# key_matrix.net
KiCad netlist of a schematic drawn in Altium Designer
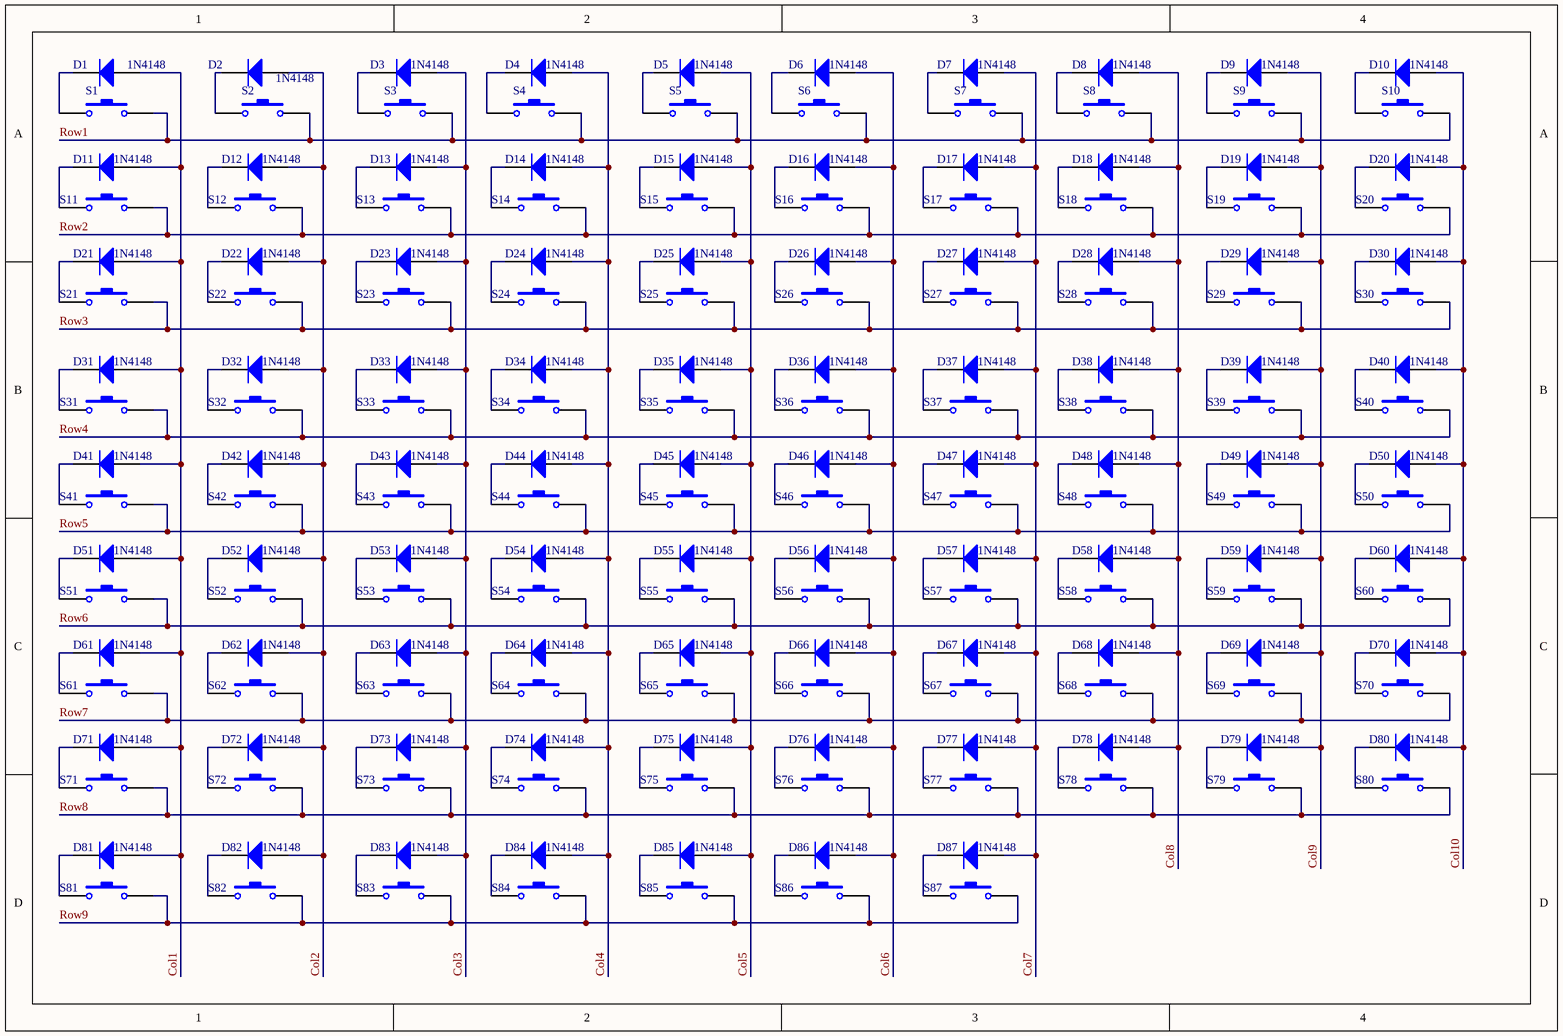
[diagram p0: key_matrix.SchDoc]

(export (version "E")
  (design (tool "Eeschema 10.0.6"))
  (components
    (comp (ref "D1")
      (value "1N4148")
      (footprint "SOD-80")
      (description "High Conductance Fast Diode")
      (fields (field (name "PUBLISHER") "Altium Limited"))
      (libsource (lib "Miscellaneous Devices") (part "Diode 1N4148"))
    )
    (comp (ref "D2")
      (value "1N4148")
      (footprint "SOD-80")
      (description "High Conductance Fast Diode")
      (fields (field (name "PUBLISHER") "Altium Limited"))
      (libsource (lib "Miscellaneous Devices") (part "Diode 1N4148"))
    )
    (comp (ref "D3")
      (value "1N4148")
      (footprint "SOD-80")
      (description "High Conductance Fast Diode")
      (fields (field (name "PUBLISHER") "Altium Limited"))
      (libsource (lib "Miscellaneous Devices") (part "Diode 1N4148"))
    )
    (comp (ref "D4")
      (value "1N4148")
      (footprint "SOD-80")
      (description "High Conductance Fast Diode")
      (fields (field (name "PUBLISHER") "Altium Limited"))
      (libsource (lib "Miscellaneous Devices") (part "Diode 1N4148"))
    )
    (comp (ref "D5")
      (value "1N4148")
      (footprint "SOD-80")
      (description "High Conductance Fast Diode")
      (fields (field (name "PUBLISHER") "Altium Limited"))
      (libsource (lib "Miscellaneous Devices") (part "Diode 1N4148"))
    )
    (comp (ref "D6")
      (value "1N4148")
      (footprint "SOD-80")
      (description "High Conductance Fast Diode")
      (fields (field (name "PUBLISHER") "Altium Limited"))
      (libsource (lib "Miscellaneous Devices") (part "Diode 1N4148"))
    )
    (comp (ref "D7")
      (value "1N4148")
      (footprint "SOD-80")
      (description "High Conductance Fast Diode")
      (fields (field (name "PUBLISHER") "Altium Limited"))
      (libsource (lib "Miscellaneous Devices") (part "Diode 1N4148"))
    )
    (comp (ref "D8")
      (value "1N4148")
      (footprint "SOD-80")
      (description "High Conductance Fast Diode")
      (fields (field (name "PUBLISHER") "Altium Limited"))
      (libsource (lib "Miscellaneous Devices") (part "Diode 1N4148"))
    )
    (comp (ref "D9")
      (value "1N4148")
      (footprint "SOD-80")
      (description "High Conductance Fast Diode")
      (fields (field (name "PUBLISHER") "Altium Limited"))
      (libsource (lib "Miscellaneous Devices") (part "Diode 1N4148"))
    )
    (comp (ref "D10")
      (value "1N4148")
      (footprint "SOD-80")
      (description "High Conductance Fast Diode")
      (fields (field (name "PUBLISHER") "Altium Limited"))
      (libsource (lib "Miscellaneous Devices") (part "Diode 1N4148"))
    )
    (comp (ref "D11")
      (value "1N4148")
      (footprint "SOD-80")
      (description "High Conductance Fast Diode")
      (fields (field (name "PUBLISHER") "Altium Limited"))
      (libsource (lib "Miscellaneous Devices") (part "Diode 1N4148"))
    )
    (comp (ref "D12")
      (value "1N4148")
      (footprint "SOD-80")
      (description "High Conductance Fast Diode")
      (fields (field (name "PUBLISHER") "Altium Limited"))
      (libsource (lib "Miscellaneous Devices") (part "Diode 1N4148"))
    )
    (comp (ref "D13")
      (value "1N4148")
      (footprint "SOD-80")
      (description "High Conductance Fast Diode")
      (fields (field (name "PUBLISHER") "Altium Limited"))
      (libsource (lib "Miscellaneous Devices") (part "Diode 1N4148"))
    )
    (comp (ref "D14")
      (value "1N4148")
      (footprint "SOD-80")
      (description "High Conductance Fast Diode")
      (fields (field (name "PUBLISHER") "Altium Limited"))
      (libsource (lib "Miscellaneous Devices") (part "Diode 1N4148"))
    )
    (comp (ref "D15")
      (value "1N4148")
      (footprint "SOD-80")
      (description "High Conductance Fast Diode")
      (fields (field (name "PUBLISHER") "Altium Limited"))
      (libsource (lib "Miscellaneous Devices") (part "Diode 1N4148"))
    )
    (comp (ref "D16")
      (value "1N4148")
      (footprint "SOD-80")
      (description "High Conductance Fast Diode")
      (fields (field (name "PUBLISHER") "Altium Limited"))
      (libsource (lib "Miscellaneous Devices") (part "Diode 1N4148"))
    )
    (comp (ref "D17")
      (value "1N4148")
      (footprint "SOD-80")
      (description "High Conductance Fast Diode")
      (fields (field (name "PUBLISHER") "Altium Limited"))
      (libsource (lib "Miscellaneous Devices") (part "Diode 1N4148"))
    )
    (comp (ref "D18")
      (value "1N4148")
      (footprint "SOD-80")
      (description "High Conductance Fast Diode")
      (fields (field (name "PUBLISHER") "Altium Limited"))
      (libsource (lib "Miscellaneous Devices") (part "Diode 1N4148"))
    )
    (comp (ref "D19")
      (value "1N4148")
      (footprint "SOD-80")
      (description "High Conductance Fast Diode")
      (fields (field (name "PUBLISHER") "Altium Limited"))
      (libsource (lib "Miscellaneous Devices") (part "Diode 1N4148"))
    )
    (comp (ref "D20")
      (value "1N4148")
      (footprint "SOD-80")
      (description "High Conductance Fast Diode")
      (fields (field (name "PUBLISHER") "Altium Limited"))
      (libsource (lib "Miscellaneous Devices") (part "Diode 1N4148"))
    )
    (comp (ref "D21")
      (value "1N4148")
      (footprint "SOD-80")
      (description "High Conductance Fast Diode")
      (fields (field (name "PUBLISHER") "Altium Limited"))
      (libsource (lib "Miscellaneous Devices") (part "Diode 1N4148"))
    )
    (comp (ref "D22")
      (value "1N4148")
      (footprint "SOD-80")
      (description "High Conductance Fast Diode")
      (fields (field (name "PUBLISHER") "Altium Limited"))
      (libsource (lib "Miscellaneous Devices") (part "Diode 1N4148"))
    )
    (comp (ref "D23")
      (value "1N4148")
      (footprint "SOD-80")
      (description "High Conductance Fast Diode")
      (fields (field (name "PUBLISHER") "Altium Limited"))
      (libsource (lib "Miscellaneous Devices") (part "Diode 1N4148"))
    )
    (comp (ref "D24")
      (value "1N4148")
      (footprint "SOD-80")
      (description "High Conductance Fast Diode")
      (fields (field (name "PUBLISHER") "Altium Limited"))
      (libsource (lib "Miscellaneous Devices") (part "Diode 1N4148"))
    )
    (comp (ref "D25")
      (value "1N4148")
      (footprint "SOD-80")
      (description "High Conductance Fast Diode")
      (fields (field (name "PUBLISHER") "Altium Limited"))
      (libsource (lib "Miscellaneous Devices") (part "Diode 1N4148"))
    )
    (comp (ref "D26")
      (value "1N4148")
      (footprint "SOD-80")
      (description "High Conductance Fast Diode")
      (fields (field (name "PUBLISHER") "Altium Limited"))
      (libsource (lib "Miscellaneous Devices") (part "Diode 1N4148"))
    )
    (comp (ref "D27")
      (value "1N4148")
      (footprint "SOD-80")
      (description "High Conductance Fast Diode")
      (fields (field (name "PUBLISHER") "Altium Limited"))
      (libsource (lib "Miscellaneous Devices") (part "Diode 1N4148"))
    )
    (comp (ref "D28")
      (value "1N4148")
      (footprint "SOD-80")
      (description "High Conductance Fast Diode")
      (fields (field (name "PUBLISHER") "Altium Limited"))
      (libsource (lib "Miscellaneous Devices") (part "Diode 1N4148"))
    )
    (comp (ref "D29")
      (value "1N4148")
      (footprint "SOD-80")
      (description "High Conductance Fast Diode")
      (fields (field (name "PUBLISHER") "Altium Limited"))
      (libsource (lib "Miscellaneous Devices") (part "Diode 1N4148"))
    )
    (comp (ref "D30")
      (value "1N4148")
      (footprint "SOD-80")
      (description "High Conductance Fast Diode")
      (fields (field (name "PUBLISHER") "Altium Limited"))
      (libsource (lib "Miscellaneous Devices") (part "Diode 1N4148"))
    )
    (comp (ref "D31")
      (value "1N4148")
      (footprint "SOD-80")
      (description "High Conductance Fast Diode")
      (fields (field (name "PUBLISHER") "Altium Limited"))
      (libsource (lib "Miscellaneous Devices") (part "Diode 1N4148"))
    )
    (comp (ref "D32")
      (value "1N4148")
      (footprint "SOD-80")
      (description "High Conductance Fast Diode")
      (fields (field (name "PUBLISHER") "Altium Limited"))
      (libsource (lib "Miscellaneous Devices") (part "Diode 1N4148"))
    )
    (comp (ref "D33")
      (value "1N4148")
      (footprint "SOD-80")
      (description "High Conductance Fast Diode")
      (fields (field (name "PUBLISHER") "Altium Limited"))
      (libsource (lib "Miscellaneous Devices") (part "Diode 1N4148"))
    )
    (comp (ref "D34")
      (value "1N4148")
      (footprint "SOD-80")
      (description "High Conductance Fast Diode")
      (fields (field (name "PUBLISHER") "Altium Limited"))
      (libsource (lib "Miscellaneous Devices") (part "Diode 1N4148"))
    )
    (comp (ref "D35")
      (value "1N4148")
      (footprint "SOD-80")
      (description "High Conductance Fast Diode")
      (fields (field (name "PUBLISHER") "Altium Limited"))
      (libsource (lib "Miscellaneous Devices") (part "Diode 1N4148"))
    )
    (comp (ref "D36")
      (value "1N4148")
      (footprint "SOD-80")
      (description "High Conductance Fast Diode")
      (fields (field (name "PUBLISHER") "Altium Limited"))
      (libsource (lib "Miscellaneous Devices") (part "Diode 1N4148"))
    )
    (comp (ref "D37")
      (value "1N4148")
      (footprint "SOD-80")
      (description "High Conductance Fast Diode")
      (fields (field (name "PUBLISHER") "Altium Limited"))
      (libsource (lib "Miscellaneous Devices") (part "Diode 1N4148"))
    )
    (comp (ref "D38")
      (value "1N4148")
      (footprint "SOD-80")
      (description "High Conductance Fast Diode")
      (fields (field (name "PUBLISHER") "Altium Limited"))
      (libsource (lib "Miscellaneous Devices") (part "Diode 1N4148"))
    )
    (comp (ref "D39")
      (value "1N4148")
      (footprint "SOD-80")
      (description "High Conductance Fast Diode")
      (fields (field (name "PUBLISHER") "Altium Limited"))
      (libsource (lib "Miscellaneous Devices") (part "Diode 1N4148"))
    )
    (comp (ref "D40")
      (value "1N4148")
      (footprint "SOD-80")
      (description "High Conductance Fast Diode")
      (fields (field (name "PUBLISHER") "Altium Limited"))
      (libsource (lib "Miscellaneous Devices") (part "Diode 1N4148"))
    )
    (comp (ref "D41")
      (value "1N4148")
      (footprint "SOD-80")
      (description "High Conductance Fast Diode")
      (fields (field (name "PUBLISHER") "Altium Limited"))
      (libsource (lib "Miscellaneous Devices") (part "Diode 1N4148"))
    )
    (comp (ref "D42")
      (value "1N4148")
      (footprint "SOD-80")
      (description "High Conductance Fast Diode")
      (fields (field (name "PUBLISHER") "Altium Limited"))
      (libsource (lib "Miscellaneous Devices") (part "Diode 1N4148"))
    )
    (comp (ref "D43")
      (value "1N4148")
      (footprint "SOD-80")
      (description "High Conductance Fast Diode")
      (fields (field (name "PUBLISHER") "Altium Limited"))
      (libsource (lib "Miscellaneous Devices") (part "Diode 1N4148"))
    )
    (comp (ref "D44")
      (value "1N4148")
      (footprint "SOD-80")
      (description "High Conductance Fast Diode")
      (fields (field (name "PUBLISHER") "Altium Limited"))
      (libsource (lib "Miscellaneous Devices") (part "Diode 1N4148"))
    )
    (comp (ref "D45")
      (value "1N4148")
      (footprint "SOD-80")
      (description "High Conductance Fast Diode")
      (fields (field (name "PUBLISHER") "Altium Limited"))
      (libsource (lib "Miscellaneous Devices") (part "Diode 1N4148"))
    )
    (comp (ref "D46")
      (value "1N4148")
      (footprint "SOD-80")
      (description "High Conductance Fast Diode")
      (fields (field (name "PUBLISHER") "Altium Limited"))
      (libsource (lib "Miscellaneous Devices") (part "Diode 1N4148"))
    )
    (comp (ref "D47")
      (value "1N4148")
      (footprint "SOD-80")
      (description "High Conductance Fast Diode")
      (fields (field (name "PUBLISHER") "Altium Limited"))
      (libsource (lib "Miscellaneous Devices") (part "Diode 1N4148"))
    )
    (comp (ref "D48")
      (value "1N4148")
      (footprint "SOD-80")
      (description "High Conductance Fast Diode")
      (fields (field (name "PUBLISHER") "Altium Limited"))
      (libsource (lib "Miscellaneous Devices") (part "Diode 1N4148"))
    )
    (comp (ref "D49")
      (value "1N4148")
      (footprint "SOD-80")
      (description "High Conductance Fast Diode")
      (fields (field (name "PUBLISHER") "Altium Limited"))
      (libsource (lib "Miscellaneous Devices") (part "Diode 1N4148"))
    )
    (comp (ref "D50")
      (value "1N4148")
      (footprint "SOD-80")
      (description "High Conductance Fast Diode")
      (fields (field (name "PUBLISHER") "Altium Limited"))
      (libsource (lib "Miscellaneous Devices") (part "Diode 1N4148"))
    )
    (comp (ref "D51")
      (value "1N4148")
      (footprint "SOD-80")
      (description "High Conductance Fast Diode")
      (fields (field (name "PUBLISHER") "Altium Limited"))
      (libsource (lib "Miscellaneous Devices") (part "Diode 1N4148"))
    )
    (comp (ref "D52")
      (value "1N4148")
      (footprint "SOD-80")
      (description "High Conductance Fast Diode")
      (fields (field (name "PUBLISHER") "Altium Limited"))
      (libsource (lib "Miscellaneous Devices") (part "Diode 1N4148"))
    )
    (comp (ref "D53")
      (value "1N4148")
      (footprint "SOD-80")
      (description "High Conductance Fast Diode")
      (fields (field (name "PUBLISHER") "Altium Limited"))
      (libsource (lib "Miscellaneous Devices") (part "Diode 1N4148"))
    )
    (comp (ref "D54")
      (value "1N4148")
      (footprint "SOD-80")
      (description "High Conductance Fast Diode")
      (fields (field (name "PUBLISHER") "Altium Limited"))
      (libsource (lib "Miscellaneous Devices") (part "Diode 1N4148"))
    )
    (comp (ref "D55")
      (value "1N4148")
      (footprint "SOD-80")
      (description "High Conductance Fast Diode")
      (fields (field (name "PUBLISHER") "Altium Limited"))
      (libsource (lib "Miscellaneous Devices") (part "Diode 1N4148"))
    )
    (comp (ref "D56")
      (value "1N4148")
      (footprint "SOD-80")
      (description "High Conductance Fast Diode")
      (fields (field (name "PUBLISHER") "Altium Limited"))
      (libsource (lib "Miscellaneous Devices") (part "Diode 1N4148"))
    )
    (comp (ref "D57")
      (value "1N4148")
      (footprint "SOD-80")
      (description "High Conductance Fast Diode")
      (fields (field (name "PUBLISHER") "Altium Limited"))
      (libsource (lib "Miscellaneous Devices") (part "Diode 1N4148"))
    )
    (comp (ref "D58")
      (value "1N4148")
      (footprint "SOD-80")
      (description "High Conductance Fast Diode")
      (fields (field (name "PUBLISHER") "Altium Limited"))
      (libsource (lib "Miscellaneous Devices") (part "Diode 1N4148"))
    )
    (comp (ref "D59")
      (value "1N4148")
      (footprint "SOD-80")
      (description "High Conductance Fast Diode")
      (fields (field (name "PUBLISHER") "Altium Limited"))
      (libsource (lib "Miscellaneous Devices") (part "Diode 1N4148"))
    )
    (comp (ref "D60")
      (value "1N4148")
      (footprint "SOD-80")
      (description "High Conductance Fast Diode")
      (fields (field (name "PUBLISHER") "Altium Limited"))
      (libsource (lib "Miscellaneous Devices") (part "Diode 1N4148"))
    )
    (comp (ref "D61")
      (value "1N4148")
      (footprint "SOD-80")
      (description "High Conductance Fast Diode")
      (fields (field (name "PUBLISHER") "Altium Limited"))
      (libsource (lib "Miscellaneous Devices") (part "Diode 1N4148"))
    )
    (comp (ref "D62")
      (value "1N4148")
      (footprint "SOD-80")
      (description "High Conductance Fast Diode")
      (fields (field (name "PUBLISHER") "Altium Limited"))
      (libsource (lib "Miscellaneous Devices") (part "Diode 1N4148"))
    )
    (comp (ref "D63")
      (value "1N4148")
      (footprint "SOD-80")
      (description "High Conductance Fast Diode")
      (fields (field (name "PUBLISHER") "Altium Limited"))
      (libsource (lib "Miscellaneous Devices") (part "Diode 1N4148"))
    )
    (comp (ref "D64")
      (value "1N4148")
      (footprint "SOD-80")
      (description "High Conductance Fast Diode")
      (fields (field (name "PUBLISHER") "Altium Limited"))
      (libsource (lib "Miscellaneous Devices") (part "Diode 1N4148"))
    )
    (comp (ref "D65")
      (value "1N4148")
      (footprint "SOD-80")
      (description "High Conductance Fast Diode")
      (fields (field (name "PUBLISHER") "Altium Limited"))
      (libsource (lib "Miscellaneous Devices") (part "Diode 1N4148"))
    )
    (comp (ref "D66")
      (value "1N4148")
      (footprint "SOD-80")
      (description "High Conductance Fast Diode")
      (fields (field (name "PUBLISHER") "Altium Limited"))
      (libsource (lib "Miscellaneous Devices") (part "Diode 1N4148"))
    )
    (comp (ref "D67")
      (value "1N4148")
      (footprint "SOD-80")
      (description "High Conductance Fast Diode")
      (fields (field (name "PUBLISHER") "Altium Limited"))
      (libsource (lib "Miscellaneous Devices") (part "Diode 1N4148"))
    )
    (comp (ref "D68")
      (value "1N4148")
      (footprint "SOD-80")
      (description "High Conductance Fast Diode")
      (fields (field (name "PUBLISHER") "Altium Limited"))
      (libsource (lib "Miscellaneous Devices") (part "Diode 1N4148"))
    )
    (comp (ref "D69")
      (value "1N4148")
      (footprint "SOD-80")
      (description "High Conductance Fast Diode")
      (fields (field (name "PUBLISHER") "Altium Limited"))
      (libsource (lib "Miscellaneous Devices") (part "Diode 1N4148"))
    )
    (comp (ref "D70")
      (value "1N4148")
      (footprint "SOD-80")
      (description "High Conductance Fast Diode")
      (fields (field (name "PUBLISHER") "Altium Limited"))
      (libsource (lib "Miscellaneous Devices") (part "Diode 1N4148"))
    )
    (comp (ref "D71")
      (value "1N4148")
      (footprint "SOD-80")
      (description "High Conductance Fast Diode")
      (fields (field (name "PUBLISHER") "Altium Limited"))
      (libsource (lib "Miscellaneous Devices") (part "Diode 1N4148"))
    )
    (comp (ref "D72")
      (value "1N4148")
      (footprint "SOD-80")
      (description "High Conductance Fast Diode")
      (fields (field (name "PUBLISHER") "Altium Limited"))
      (libsource (lib "Miscellaneous Devices") (part "Diode 1N4148"))
    )
    (comp (ref "D73")
      (value "1N4148")
      (footprint "SOD-80")
      (description "High Conductance Fast Diode")
      (fields (field (name "PUBLISHER") "Altium Limited"))
      (libsource (lib "Miscellaneous Devices") (part "Diode 1N4148"))
    )
    (comp (ref "D74")
      (value "1N4148")
      (footprint "SOD-80")
      (description "High Conductance Fast Diode")
      (fields (field (name "PUBLISHER") "Altium Limited"))
      (libsource (lib "Miscellaneous Devices") (part "Diode 1N4148"))
    )
    (comp (ref "D75")
      (value "1N4148")
      (footprint "SOD-80")
      (description "High Conductance Fast Diode")
      (fields (field (name "PUBLISHER") "Altium Limited"))
      (libsource (lib "Miscellaneous Devices") (part "Diode 1N4148"))
    )
    (comp (ref "D76")
      (value "1N4148")
      (footprint "SOD-80")
      (description "High Conductance Fast Diode")
      (fields (field (name "PUBLISHER") "Altium Limited"))
      (libsource (lib "Miscellaneous Devices") (part "Diode 1N4148"))
    )
    (comp (ref "D77")
      (value "1N4148")
      (footprint "SOD-80")
      (description "High Conductance Fast Diode")
      (fields (field (name "PUBLISHER") "Altium Limited"))
      (libsource (lib "Miscellaneous Devices") (part "Diode 1N4148"))
    )
    (comp (ref "D78")
      (value "1N4148")
      (footprint "SOD-80")
      (description "High Conductance Fast Diode")
      (fields (field (name "PUBLISHER") "Altium Limited"))
      (libsource (lib "Miscellaneous Devices") (part "Diode 1N4148"))
    )
    (comp (ref "D79")
      (value "1N4148")
      (footprint "SOD-80")
      (description "High Conductance Fast Diode")
      (fields (field (name "PUBLISHER") "Altium Limited"))
      (libsource (lib "Miscellaneous Devices") (part "Diode 1N4148"))
    )
    (comp (ref "D80")
      (value "1N4148")
      (footprint "SOD-80")
      (description "High Conductance Fast Diode")
      (fields (field (name "PUBLISHER") "Altium Limited"))
      (libsource (lib "Miscellaneous Devices") (part "Diode 1N4148"))
    )
    (comp (ref "D81")
      (value "1N4148")
      (footprint "SOD-80")
      (description "High Conductance Fast Diode")
      (fields (field (name "PUBLISHER") "Altium Limited"))
      (libsource (lib "Miscellaneous Devices") (part "Diode 1N4148"))
    )
    (comp (ref "D82")
      (value "1N4148")
      (footprint "SOD-80")
      (description "High Conductance Fast Diode")
      (fields (field (name "PUBLISHER") "Altium Limited"))
      (libsource (lib "Miscellaneous Devices") (part "Diode 1N4148"))
    )
    (comp (ref "D83")
      (value "1N4148")
      (footprint "SOD-80")
      (description "High Conductance Fast Diode")
      (fields (field (name "PUBLISHER") "Altium Limited"))
      (libsource (lib "Miscellaneous Devices") (part "Diode 1N4148"))
    )
    (comp (ref "D84")
      (value "1N4148")
      (footprint "SOD-80")
      (description "High Conductance Fast Diode")
      (fields (field (name "PUBLISHER") "Altium Limited"))
      (libsource (lib "Miscellaneous Devices") (part "Diode 1N4148"))
    )
    (comp (ref "D85")
      (value "1N4148")
      (footprint "SOD-80")
      (description "High Conductance Fast Diode")
      (fields (field (name "PUBLISHER") "Altium Limited"))
      (libsource (lib "Miscellaneous Devices") (part "Diode 1N4148"))
    )
    (comp (ref "D86")
      (value "1N4148")
      (footprint "SOD-80")
      (description "High Conductance Fast Diode")
      (fields (field (name "PUBLISHER") "Altium Limited"))
      (libsource (lib "Miscellaneous Devices") (part "Diode 1N4148"))
    )
    (comp (ref "D87")
      (value "1N4148")
      (footprint "SOD-80")
      (description "High Conductance Fast Diode")
      (fields (field (name "PUBLISHER") "Altium Limited"))
      (libsource (lib "Miscellaneous Devices") (part "Diode 1N4148"))
    )
    (comp (ref "S1")
      (value "SW-PB")
      (footprint "MX_SW-1")
      (description "Switch")
      (fields (field (name "PUBLISHER") "Altium Limited"))
      (libsource (lib "Miscellaneous Devices") (part "SW-PB"))
    )
    (comp (ref "S2")
      (value "SW-PB")
      (footprint "MX_SW-1")
      (description "Switch")
      (fields (field (name "PUBLISHER") "Altium Limited"))
      (libsource (lib "Miscellaneous Devices") (part "SW-PB"))
    )
    (comp (ref "S3")
      (value "SW-PB")
      (footprint "MX_SW-1")
      (description "Switch")
      (fields (field (name "PUBLISHER") "Altium Limited"))
      (libsource (lib "Miscellaneous Devices") (part "SW-PB"))
    )
    (comp (ref "S4")
      (value "SW-PB")
      (footprint "MX_SW-1")
      (description "Switch")
      (fields (field (name "PUBLISHER") "Altium Limited"))
      (libsource (lib "Miscellaneous Devices") (part "SW-PB"))
    )
    (comp (ref "S5")
      (value "SW-PB")
      (footprint "MX_SW-1")
      (description "Switch")
      (fields (field (name "PUBLISHER") "Altium Limited"))
      (libsource (lib "Miscellaneous Devices") (part "SW-PB"))
    )
    (comp (ref "S6")
      (value "SW-PB")
      (footprint "MX_SW-1")
      (description "Switch")
      (fields (field (name "PUBLISHER") "Altium Limited"))
      (libsource (lib "Miscellaneous Devices") (part "SW-PB"))
    )
    (comp (ref "S7")
      (value "SW-PB")
      (footprint "MX_SW-1")
      (description "Switch")
      (fields (field (name "PUBLISHER") "Altium Limited"))
      (libsource (lib "Miscellaneous Devices") (part "SW-PB"))
    )
    (comp (ref "S8")
      (value "SW-PB")
      (footprint "MX_SW-1")
      (description "Switch")
      (fields (field (name "PUBLISHER") "Altium Limited"))
      (libsource (lib "Miscellaneous Devices") (part "SW-PB"))
    )
    (comp (ref "S9")
      (value "SW-PB")
      (footprint "MX_SW-1")
      (description "Switch")
      (fields (field (name "PUBLISHER") "Altium Limited"))
      (libsource (lib "Miscellaneous Devices") (part "SW-PB"))
    )
    (comp (ref "S10")
      (value "SW-PB")
      (footprint "MX_SW-1")
      (description "Switch")
      (fields (field (name "PUBLISHER") "Altium Limited"))
      (libsource (lib "Miscellaneous Devices") (part "SW-PB"))
    )
    (comp (ref "S11")
      (value "SW-PB")
      (footprint "MX_SW-1")
      (description "Switch")
      (fields (field (name "PUBLISHER") "Altium Limited"))
      (libsource (lib "Miscellaneous Devices") (part "SW-PB"))
    )
    (comp (ref "S12")
      (value "SW-PB")
      (footprint "MX_SW-1")
      (description "Switch")
      (fields (field (name "PUBLISHER") "Altium Limited"))
      (libsource (lib "Miscellaneous Devices") (part "SW-PB"))
    )
    (comp (ref "S13")
      (value "SW-PB")
      (footprint "MX_SW-1")
      (description "Switch")
      (fields (field (name "PUBLISHER") "Altium Limited"))
      (libsource (lib "Miscellaneous Devices") (part "SW-PB"))
    )
    (comp (ref "S14")
      (value "SW-PB")
      (footprint "MX_SW-1")
      (description "Switch")
      (fields (field (name "PUBLISHER") "Altium Limited"))
      (libsource (lib "Miscellaneous Devices") (part "SW-PB"))
    )
    (comp (ref "S15")
      (value "SW-PB")
      (footprint "MX_SW-1")
      (description "Switch")
      (fields (field (name "PUBLISHER") "Altium Limited"))
      (libsource (lib "Miscellaneous Devices") (part "SW-PB"))
    )
    (comp (ref "S16")
      (value "SW-PB")
      (footprint "MX_SW-1")
      (description "Switch")
      (fields (field (name "PUBLISHER") "Altium Limited"))
      (libsource (lib "Miscellaneous Devices") (part "SW-PB"))
    )
    (comp (ref "S17")
      (value "SW-PB")
      (footprint "MX_SW-1")
      (description "Switch")
      (fields (field (name "PUBLISHER") "Altium Limited"))
      (libsource (lib "Miscellaneous Devices") (part "SW-PB"))
    )
    (comp (ref "S18")
      (value "SW-PB")
      (footprint "MX_SW-1")
      (description "Switch")
      (fields (field (name "PUBLISHER") "Altium Limited"))
      (libsource (lib "Miscellaneous Devices") (part "SW-PB"))
    )
    (comp (ref "S19")
      (value "SW-PB")
      (footprint "MX_SW-1")
      (description "Switch")
      (fields (field (name "PUBLISHER") "Altium Limited"))
      (libsource (lib "Miscellaneous Devices") (part "SW-PB"))
    )
    (comp (ref "S20")
      (value "SW-PB")
      (footprint "MX_SW-1")
      (description "Switch")
      (fields (field (name "PUBLISHER") "Altium Limited"))
      (libsource (lib "Miscellaneous Devices") (part "SW-PB"))
    )
    (comp (ref "S21")
      (value "SW-PB")
      (footprint "MX_SW-1")
      (description "Switch")
      (fields (field (name "PUBLISHER") "Altium Limited"))
      (libsource (lib "Miscellaneous Devices") (part "SW-PB"))
    )
    (comp (ref "S22")
      (value "SW-PB")
      (footprint "MX_SW-1")
      (description "Switch")
      (fields (field (name "PUBLISHER") "Altium Limited"))
      (libsource (lib "Miscellaneous Devices") (part "SW-PB"))
    )
    (comp (ref "S23")
      (value "SW-PB")
      (footprint "MX_SW-1")
      (description "Switch")
      (fields (field (name "PUBLISHER") "Altium Limited"))
      (libsource (lib "Miscellaneous Devices") (part "SW-PB"))
    )
    (comp (ref "S24")
      (value "SW-PB")
      (footprint "MX_SW-1")
      (description "Switch")
      (fields (field (name "PUBLISHER") "Altium Limited"))
      (libsource (lib "Miscellaneous Devices") (part "SW-PB"))
    )
    (comp (ref "S25")
      (value "SW-PB")
      (footprint "MX_SW-1")
      (description "Switch")
      (fields (field (name "PUBLISHER") "Altium Limited"))
      (libsource (lib "Miscellaneous Devices") (part "SW-PB"))
    )
    (comp (ref "S26")
      (value "SW-PB")
      (footprint "MX_SW-1")
      (description "Switch")
      (fields (field (name "PUBLISHER") "Altium Limited"))
      (libsource (lib "Miscellaneous Devices") (part "SW-PB"))
    )
    (comp (ref "S27")
      (value "SW-PB")
      (footprint "MX_SW-1")
      (description "Switch")
      (fields (field (name "PUBLISHER") "Altium Limited"))
      (libsource (lib "Miscellaneous Devices") (part "SW-PB"))
    )
    (comp (ref "S28")
      (value "SW-PB")
      (footprint "MX_SW-1")
      (description "Switch")
      (fields (field (name "PUBLISHER") "Altium Limited"))
      (libsource (lib "Miscellaneous Devices") (part "SW-PB"))
    )
    (comp (ref "S29")
      (value "SW-PB")
      (footprint "MX_SW-1")
      (description "Switch")
      (fields (field (name "PUBLISHER") "Altium Limited"))
      (libsource (lib "Miscellaneous Devices") (part "SW-PB"))
    )
    (comp (ref "S30")
      (value "SW-PB")
      (footprint "MX_SW-1")
      (description "Switch")
      (fields (field (name "PUBLISHER") "Altium Limited"))
      (libsource (lib "Miscellaneous Devices") (part "SW-PB"))
    )
    (comp (ref "S31")
      (value "SW-PB")
      (footprint "MX_SW-1")
      (description "Switch")
      (fields (field (name "PUBLISHER") "Altium Limited"))
      (libsource (lib "Miscellaneous Devices") (part "SW-PB"))
    )
    (comp (ref "S32")
      (value "SW-PB")
      (footprint "MX_SW-1")
      (description "Switch")
      (fields (field (name "PUBLISHER") "Altium Limited"))
      (libsource (lib "Miscellaneous Devices") (part "SW-PB"))
    )
    (comp (ref "S33")
      (value "SW-PB")
      (footprint "MX_SW-1")
      (description "Switch")
      (fields (field (name "PUBLISHER") "Altium Limited"))
      (libsource (lib "Miscellaneous Devices") (part "SW-PB"))
    )
    (comp (ref "S34")
      (value "SW-PB")
      (footprint "MX_SW-1")
      (description "Switch")
      (fields (field (name "PUBLISHER") "Altium Limited"))
      (libsource (lib "Miscellaneous Devices") (part "SW-PB"))
    )
    (comp (ref "S35")
      (value "SW-PB")
      (footprint "MX_SW-1")
      (description "Switch")
      (fields (field (name "PUBLISHER") "Altium Limited"))
      (libsource (lib "Miscellaneous Devices") (part "SW-PB"))
    )
    (comp (ref "S36")
      (value "SW-PB")
      (footprint "MX_SW-1")
      (description "Switch")
      (fields (field (name "PUBLISHER") "Altium Limited"))
      (libsource (lib "Miscellaneous Devices") (part "SW-PB"))
    )
    (comp (ref "S37")
      (value "SW-PB")
      (footprint "MX_SW-1")
      (description "Switch")
      (fields (field (name "PUBLISHER") "Altium Limited"))
      (libsource (lib "Miscellaneous Devices") (part "SW-PB"))
    )
    (comp (ref "S38")
      (value "SW-PB")
      (footprint "MX_SW-1")
      (description "Switch")
      (fields (field (name "PUBLISHER") "Altium Limited"))
      (libsource (lib "Miscellaneous Devices") (part "SW-PB"))
    )
    (comp (ref "S39")
      (value "SW-PB")
      (footprint "MX_SW-1")
      (description "Switch")
      (fields (field (name "PUBLISHER") "Altium Limited"))
      (libsource (lib "Miscellaneous Devices") (part "SW-PB"))
    )
    (comp (ref "S40")
      (value "SW-PB")
      (footprint "MX_SW-1")
      (description "Switch")
      (fields (field (name "PUBLISHER") "Altium Limited"))
      (libsource (lib "Miscellaneous Devices") (part "SW-PB"))
    )
    (comp (ref "S41")
      (value "SW-PB")
      (footprint "MX_SW-1")
      (description "Switch")
      (fields (field (name "PUBLISHER") "Altium Limited"))
      (libsource (lib "Miscellaneous Devices") (part "SW-PB"))
    )
    (comp (ref "S42")
      (value "SW-PB")
      (footprint "MX_SW-1")
      (description "Switch")
      (fields (field (name "PUBLISHER") "Altium Limited"))
      (libsource (lib "Miscellaneous Devices") (part "SW-PB"))
    )
    (comp (ref "S43")
      (value "SW-PB")
      (footprint "MX_SW-1")
      (description "Switch")
      (fields (field (name "PUBLISHER") "Altium Limited"))
      (libsource (lib "Miscellaneous Devices") (part "SW-PB"))
    )
    (comp (ref "S44")
      (value "SW-PB")
      (footprint "MX_SW-1")
      (description "Switch")
      (fields (field (name "PUBLISHER") "Altium Limited"))
      (libsource (lib "Miscellaneous Devices") (part "SW-PB"))
    )
    (comp (ref "S45")
      (value "SW-PB")
      (footprint "MX_SW-1")
      (description "Switch")
      (fields (field (name "PUBLISHER") "Altium Limited"))
      (libsource (lib "Miscellaneous Devices") (part "SW-PB"))
    )
    (comp (ref "S46")
      (value "SW-PB")
      (footprint "MX_SW-1")
      (description "Switch")
      (fields (field (name "PUBLISHER") "Altium Limited"))
      (libsource (lib "Miscellaneous Devices") (part "SW-PB"))
    )
    (comp (ref "S47")
      (value "SW-PB")
      (footprint "MX_SW-1")
      (description "Switch")
      (fields (field (name "PUBLISHER") "Altium Limited"))
      (libsource (lib "Miscellaneous Devices") (part "SW-PB"))
    )
    (comp (ref "S48")
      (value "SW-PB")
      (footprint "MX_SW-1")
      (description "Switch")
      (fields (field (name "PUBLISHER") "Altium Limited"))
      (libsource (lib "Miscellaneous Devices") (part "SW-PB"))
    )
    (comp (ref "S49")
      (value "SW-PB")
      (footprint "MX_SW-1")
      (description "Switch")
      (fields (field (name "PUBLISHER") "Altium Limited"))
      (libsource (lib "Miscellaneous Devices") (part "SW-PB"))
    )
    (comp (ref "S50")
      (value "SW-PB")
      (footprint "MX_SW-1")
      (description "Switch")
      (fields (field (name "PUBLISHER") "Altium Limited"))
      (libsource (lib "Miscellaneous Devices") (part "SW-PB"))
    )
    (comp (ref "S51")
      (value "SW-PB")
      (footprint "MX_SW-1")
      (description "Switch")
      (fields (field (name "PUBLISHER") "Altium Limited"))
      (libsource (lib "Miscellaneous Devices") (part "SW-PB"))
    )
    (comp (ref "S52")
      (value "SW-PB")
      (footprint "MX_SW-1")
      (description "Switch")
      (fields (field (name "PUBLISHER") "Altium Limited"))
      (libsource (lib "Miscellaneous Devices") (part "SW-PB"))
    )
    (comp (ref "S53")
      (value "SW-PB")
      (footprint "MX_SW-1")
      (description "Switch")
      (fields (field (name "PUBLISHER") "Altium Limited"))
      (libsource (lib "Miscellaneous Devices") (part "SW-PB"))
    )
    (comp (ref "S54")
      (value "SW-PB")
      (footprint "MX_SW-1")
      (description "Switch")
      (fields (field (name "PUBLISHER") "Altium Limited"))
      (libsource (lib "Miscellaneous Devices") (part "SW-PB"))
    )
    (comp (ref "S55")
      (value "SW-PB")
      (footprint "MX_SW-1")
      (description "Switch")
      (fields (field (name "PUBLISHER") "Altium Limited"))
      (libsource (lib "Miscellaneous Devices") (part "SW-PB"))
    )
    (comp (ref "S56")
      (value "SW-PB")
      (footprint "MX_SW-1")
      (description "Switch")
      (fields (field (name "PUBLISHER") "Altium Limited"))
      (libsource (lib "Miscellaneous Devices") (part "SW-PB"))
    )
    (comp (ref "S57")
      (value "SW-PB")
      (footprint "MX_SW-1")
      (description "Switch")
      (fields (field (name "PUBLISHER") "Altium Limited"))
      (libsource (lib "Miscellaneous Devices") (part "SW-PB"))
    )
    (comp (ref "S58")
      (value "SW-PB")
      (footprint "MX_SW-1")
      (description "Switch")
      (fields (field (name "PUBLISHER") "Altium Limited"))
      (libsource (lib "Miscellaneous Devices") (part "SW-PB"))
    )
    (comp (ref "S59")
      (value "SW-PB")
      (footprint "MX_SW-1")
      (description "Switch")
      (fields (field (name "PUBLISHER") "Altium Limited"))
      (libsource (lib "Miscellaneous Devices") (part "SW-PB"))
    )
    (comp (ref "S60")
      (value "SW-PB")
      (footprint "MX_SW-1")
      (description "Switch")
      (fields (field (name "PUBLISHER") "Altium Limited"))
      (libsource (lib "Miscellaneous Devices") (part "SW-PB"))
    )
    (comp (ref "S61")
      (value "SW-PB")
      (footprint "MX_SW-1")
      (description "Switch")
      (fields (field (name "PUBLISHER") "Altium Limited"))
      (libsource (lib "Miscellaneous Devices") (part "SW-PB"))
    )
    (comp (ref "S62")
      (value "SW-PB")
      (footprint "MX_SW-1")
      (description "Switch")
      (fields (field (name "PUBLISHER") "Altium Limited"))
      (libsource (lib "Miscellaneous Devices") (part "SW-PB"))
    )
    (comp (ref "S63")
      (value "SW-PB")
      (footprint "MX_SW-1")
      (description "Switch")
      (fields (field (name "PUBLISHER") "Altium Limited"))
      (libsource (lib "Miscellaneous Devices") (part "SW-PB"))
    )
    (comp (ref "S64")
      (value "SW-PB")
      (footprint "MX_SW-1")
      (description "Switch")
      (fields (field (name "PUBLISHER") "Altium Limited"))
      (libsource (lib "Miscellaneous Devices") (part "SW-PB"))
    )
    (comp (ref "S65")
      (value "SW-PB")
      (footprint "MX_SW-1")
      (description "Switch")
      (fields (field (name "PUBLISHER") "Altium Limited"))
      (libsource (lib "Miscellaneous Devices") (part "SW-PB"))
    )
    (comp (ref "S66")
      (value "SW-PB")
      (footprint "MX_SW-1")
      (description "Switch")
      (fields (field (name "PUBLISHER") "Altium Limited"))
      (libsource (lib "Miscellaneous Devices") (part "SW-PB"))
    )
    (comp (ref "S67")
      (value "SW-PB")
      (footprint "MX_SW-1")
      (description "Switch")
      (fields (field (name "PUBLISHER") "Altium Limited"))
      (libsource (lib "Miscellaneous Devices") (part "SW-PB"))
    )
    (comp (ref "S68")
      (value "SW-PB")
      (footprint "MX_SW-1")
      (description "Switch")
      (fields (field (name "PUBLISHER") "Altium Limited"))
      (libsource (lib "Miscellaneous Devices") (part "SW-PB"))
    )
    (comp (ref "S69")
      (value "SW-PB")
      (footprint "MX_SW-1")
      (description "Switch")
      (fields (field (name "PUBLISHER") "Altium Limited"))
      (libsource (lib "Miscellaneous Devices") (part "SW-PB"))
    )
    (comp (ref "S70")
      (value "SW-PB")
      (footprint "MX_SW-1")
      (description "Switch")
      (fields (field (name "PUBLISHER") "Altium Limited"))
      (libsource (lib "Miscellaneous Devices") (part "SW-PB"))
    )
    (comp (ref "S71")
      (value "SW-PB")
      (footprint "MX_SW-1")
      (description "Switch")
      (fields (field (name "PUBLISHER") "Altium Limited"))
      (libsource (lib "Miscellaneous Devices") (part "SW-PB"))
    )
    (comp (ref "S72")
      (value "SW-PB")
      (footprint "MX_SW-1")
      (description "Switch")
      (fields (field (name "PUBLISHER") "Altium Limited"))
      (libsource (lib "Miscellaneous Devices") (part "SW-PB"))
    )
    (comp (ref "S73")
      (value "SW-PB")
      (footprint "MX_SW-1")
      (description "Switch")
      (fields (field (name "PUBLISHER") "Altium Limited"))
      (libsource (lib "Miscellaneous Devices") (part "SW-PB"))
    )
    (comp (ref "S74")
      (value "SW-PB")
      (footprint "MX_SW-1")
      (description "Switch")
      (fields (field (name "PUBLISHER") "Altium Limited"))
      (libsource (lib "Miscellaneous Devices") (part "SW-PB"))
    )
    (comp (ref "S75")
      (value "SW-PB")
      (footprint "MX_SW-1")
      (description "Switch")
      (fields (field (name "PUBLISHER") "Altium Limited"))
      (libsource (lib "Miscellaneous Devices") (part "SW-PB"))
    )
    (comp (ref "S76")
      (value "SW-PB")
      (footprint "MX_SW-1")
      (description "Switch")
      (fields (field (name "PUBLISHER") "Altium Limited"))
      (libsource (lib "Miscellaneous Devices") (part "SW-PB"))
    )
    (comp (ref "S77")
      (value "SW-PB")
      (footprint "MX_SW-1")
      (description "Switch")
      (fields (field (name "PUBLISHER") "Altium Limited"))
      (libsource (lib "Miscellaneous Devices") (part "SW-PB"))
    )
    (comp (ref "S78")
      (value "SW-PB")
      (footprint "MX_SW-1")
      (description "Switch")
      (fields (field (name "PUBLISHER") "Altium Limited"))
      (libsource (lib "Miscellaneous Devices") (part "SW-PB"))
    )
    (comp (ref "S79")
      (value "SW-PB")
      (footprint "MX_SW-1")
      (description "Switch")
      (fields (field (name "PUBLISHER") "Altium Limited"))
      (libsource (lib "Miscellaneous Devices") (part "SW-PB"))
    )
    (comp (ref "S80")
      (value "SW-PB")
      (footprint "MX_SW-1")
      (description "Switch")
      (fields (field (name "PUBLISHER") "Altium Limited"))
      (libsource (lib "Miscellaneous Devices") (part "SW-PB"))
    )
    (comp (ref "S81")
      (value "SW-PB")
      (footprint "MX_SW-1")
      (description "Switch")
      (fields (field (name "PUBLISHER") "Altium Limited"))
      (libsource (lib "Miscellaneous Devices") (part "SW-PB"))
    )
    (comp (ref "S82")
      (value "SW-PB")
      (footprint "MX_SW-1")
      (description "Switch")
      (fields (field (name "PUBLISHER") "Altium Limited"))
      (libsource (lib "Miscellaneous Devices") (part "SW-PB"))
    )
    (comp (ref "S83")
      (value "SW-PB")
      (footprint "MX_SW-1")
      (description "Switch")
      (fields (field (name "PUBLISHER") "Altium Limited"))
      (libsource (lib "Miscellaneous Devices") (part "SW-PB"))
    )
    (comp (ref "S84")
      (value "SW-PB")
      (footprint "MX_SW-1")
      (description "Switch")
      (fields (field (name "PUBLISHER") "Altium Limited"))
      (libsource (lib "Miscellaneous Devices") (part "SW-PB"))
    )
    (comp (ref "S85")
      (value "SW-PB")
      (footprint "MX_SW-1")
      (description "Switch")
      (fields (field (name "PUBLISHER") "Altium Limited"))
      (libsource (lib "Miscellaneous Devices") (part "SW-PB"))
    )
    (comp (ref "S86")
      (value "SW-PB")
      (footprint "MX_SW-1")
      (description "Switch")
      (fields (field (name "PUBLISHER") "Altium Limited"))
      (libsource (lib "Miscellaneous Devices") (part "SW-PB"))
    )
    (comp (ref "S87")
      (value "SW-PB")
      (footprint "MX_SW-1")
      (description "Switch")
      (fields (field (name "PUBLISHER") "Altium Limited"))
      (libsource (lib "Miscellaneous Devices") (part "SW-PB"))
    )
  )
  (nets
    (net (code "1") (name "/Col1") (class "Default")
      (node (ref "D1") (pin "1") (pinfunction "A_1") (pintype "passive"))
      (node (ref "D11") (pin "1") (pinfunction "A_1") (pintype "passive"))
      (node (ref "D21") (pin "1") (pinfunction "A_1") (pintype "passive"))
      (node (ref "D31") (pin "1") (pinfunction "A_1") (pintype "passive"))
      (node (ref "D41") (pin "1") (pinfunction "A_1") (pintype "passive"))
      (node (ref "D51") (pin "1") (pinfunction "A_1") (pintype "passive"))
      (node (ref "D61") (pin "1") (pinfunction "A_1") (pintype "passive"))
      (node (ref "D71") (pin "1") (pinfunction "A_1") (pintype "passive"))
      (node (ref "D81") (pin "1") (pinfunction "A_1") (pintype "passive"))
    )
    (net (code "2") (name "/Col2") (class "Default")
      (node (ref "D12") (pin "1") (pinfunction "A_1") (pintype "passive"))
      (node (ref "D2") (pin "1") (pinfunction "A_1") (pintype "passive"))
      (node (ref "D22") (pin "1") (pinfunction "A_1") (pintype "passive"))
      (node (ref "D32") (pin "1") (pinfunction "A_1") (pintype "passive"))
      (node (ref "D42") (pin "1") (pinfunction "A_1") (pintype "passive"))
      (node (ref "D52") (pin "1") (pinfunction "A_1") (pintype "passive"))
      (node (ref "D62") (pin "1") (pinfunction "A_1") (pintype "passive"))
      (node (ref "D72") (pin "1") (pinfunction "A_1") (pintype "passive"))
      (node (ref "D82") (pin "1") (pinfunction "A_1") (pintype "passive"))
    )
    (net (code "3") (name "/Col3") (class "Default")
      (node (ref "D13") (pin "1") (pinfunction "A_1") (pintype "passive"))
      (node (ref "D23") (pin "1") (pinfunction "A_1") (pintype "passive"))
      (node (ref "D3") (pin "1") (pinfunction "A_1") (pintype "passive"))
      (node (ref "D33") (pin "1") (pinfunction "A_1") (pintype "passive"))
      (node (ref "D43") (pin "1") (pinfunction "A_1") (pintype "passive"))
      (node (ref "D53") (pin "1") (pinfunction "A_1") (pintype "passive"))
      (node (ref "D63") (pin "1") (pinfunction "A_1") (pintype "passive"))
      (node (ref "D73") (pin "1") (pinfunction "A_1") (pintype "passive"))
      (node (ref "D83") (pin "1") (pinfunction "A_1") (pintype "passive"))
    )
    (net (code "4") (name "/Col4") (class "Default")
      (node (ref "D14") (pin "1") (pinfunction "A_1") (pintype "passive"))
      (node (ref "D24") (pin "1") (pinfunction "A_1") (pintype "passive"))
      (node (ref "D34") (pin "1") (pinfunction "A_1") (pintype "passive"))
      (node (ref "D4") (pin "1") (pinfunction "A_1") (pintype "passive"))
      (node (ref "D44") (pin "1") (pinfunction "A_1") (pintype "passive"))
      (node (ref "D54") (pin "1") (pinfunction "A_1") (pintype "passive"))
      (node (ref "D64") (pin "1") (pinfunction "A_1") (pintype "passive"))
      (node (ref "D74") (pin "1") (pinfunction "A_1") (pintype "passive"))
      (node (ref "D84") (pin "1") (pinfunction "A_1") (pintype "passive"))
    )
    (net (code "5") (name "/Col5") (class "Default")
      (node (ref "D15") (pin "1") (pinfunction "A_1") (pintype "passive"))
      (node (ref "D25") (pin "1") (pinfunction "A_1") (pintype "passive"))
      (node (ref "D35") (pin "1") (pinfunction "A_1") (pintype "passive"))
      (node (ref "D45") (pin "1") (pinfunction "A_1") (pintype "passive"))
      (node (ref "D5") (pin "1") (pinfunction "A_1") (pintype "passive"))
      (node (ref "D55") (pin "1") (pinfunction "A_1") (pintype "passive"))
      (node (ref "D65") (pin "1") (pinfunction "A_1") (pintype "passive"))
      (node (ref "D75") (pin "1") (pinfunction "A_1") (pintype "passive"))
      (node (ref "D85") (pin "1") (pinfunction "A_1") (pintype "passive"))
    )
    (net (code "6") (name "/Col6") (class "Default")
      (node (ref "D16") (pin "1") (pinfunction "A_1") (pintype "passive"))
      (node (ref "D26") (pin "1") (pinfunction "A_1") (pintype "passive"))
      (node (ref "D36") (pin "1") (pinfunction "A_1") (pintype "passive"))
      (node (ref "D46") (pin "1") (pinfunction "A_1") (pintype "passive"))
      (node (ref "D56") (pin "1") (pinfunction "A_1") (pintype "passive"))
      (node (ref "D6") (pin "1") (pinfunction "A_1") (pintype "passive"))
      (node (ref "D66") (pin "1") (pinfunction "A_1") (pintype "passive"))
      (node (ref "D76") (pin "1") (pinfunction "A_1") (pintype "passive"))
      (node (ref "D86") (pin "1") (pinfunction "A_1") (pintype "passive"))
    )
    (net (code "7") (name "/Col7") (class "Default")
      (node (ref "D17") (pin "1") (pinfunction "A_1") (pintype "passive"))
      (node (ref "D27") (pin "1") (pinfunction "A_1") (pintype "passive"))
      (node (ref "D37") (pin "1") (pinfunction "A_1") (pintype "passive"))
      (node (ref "D47") (pin "1") (pinfunction "A_1") (pintype "passive"))
      (node (ref "D57") (pin "1") (pinfunction "A_1") (pintype "passive"))
      (node (ref "D67") (pin "1") (pinfunction "A_1") (pintype "passive"))
      (node (ref "D7") (pin "1") (pinfunction "A_1") (pintype "passive"))
      (node (ref "D77") (pin "1") (pinfunction "A_1") (pintype "passive"))
      (node (ref "D87") (pin "1") (pinfunction "A_1") (pintype "passive"))
    )
    (net (code "8") (name "/Col8") (class "Default")
      (node (ref "D18") (pin "1") (pinfunction "A_1") (pintype "passive"))
      (node (ref "D28") (pin "1") (pinfunction "A_1") (pintype "passive"))
      (node (ref "D38") (pin "1") (pinfunction "A_1") (pintype "passive"))
      (node (ref "D48") (pin "1") (pinfunction "A_1") (pintype "passive"))
      (node (ref "D58") (pin "1") (pinfunction "A_1") (pintype "passive"))
      (node (ref "D68") (pin "1") (pinfunction "A_1") (pintype "passive"))
      (node (ref "D78") (pin "1") (pinfunction "A_1") (pintype "passive"))
      (node (ref "D8") (pin "1") (pinfunction "A_1") (pintype "passive"))
    )
    (net (code "9") (name "/Col9") (class "Default")
      (node (ref "D19") (pin "1") (pinfunction "A_1") (pintype "passive"))
      (node (ref "D29") (pin "1") (pinfunction "A_1") (pintype "passive"))
      (node (ref "D39") (pin "1") (pinfunction "A_1") (pintype "passive"))
      (node (ref "D49") (pin "1") (pinfunction "A_1") (pintype "passive"))
      (node (ref "D59") (pin "1") (pinfunction "A_1") (pintype "passive"))
      (node (ref "D69") (pin "1") (pinfunction "A_1") (pintype "passive"))
      (node (ref "D79") (pin "1") (pinfunction "A_1") (pintype "passive"))
      (node (ref "D9") (pin "1") (pinfunction "A_1") (pintype "passive"))
    )
    (net (code "10") (name "/Col10") (class "Default")
      (node (ref "D10") (pin "1") (pinfunction "A_1") (pintype "passive"))
      (node (ref "D20") (pin "1") (pinfunction "A_1") (pintype "passive"))
      (node (ref "D30") (pin "1") (pinfunction "A_1") (pintype "passive"))
      (node (ref "D40") (pin "1") (pinfunction "A_1") (pintype "passive"))
      (node (ref "D50") (pin "1") (pinfunction "A_1") (pintype "passive"))
      (node (ref "D60") (pin "1") (pinfunction "A_1") (pintype "passive"))
      (node (ref "D70") (pin "1") (pinfunction "A_1") (pintype "passive"))
      (node (ref "D80") (pin "1") (pinfunction "A_1") (pintype "passive"))
    )
    (net (code "11") (name "/Row1") (class "Default")
      (node (ref "S1") (pin "2") (pinfunction "2_2") (pintype "passive"))
      (node (ref "S10") (pin "2") (pinfunction "2_2") (pintype "passive"))
      (node (ref "S2") (pin "2") (pinfunction "2_2") (pintype "passive"))
      (node (ref "S3") (pin "2") (pinfunction "2_2") (pintype "passive"))
      (node (ref "S4") (pin "2") (pinfunction "2_2") (pintype "passive"))
      (node (ref "S5") (pin "2") (pinfunction "2_2") (pintype "passive"))
      (node (ref "S6") (pin "2") (pinfunction "2_2") (pintype "passive"))
      (node (ref "S7") (pin "2") (pinfunction "2_2") (pintype "passive"))
      (node (ref "S8") (pin "2") (pinfunction "2_2") (pintype "passive"))
      (node (ref "S9") (pin "2") (pinfunction "2_2") (pintype "passive"))
    )
    (net (code "12") (name "/Row2") (class "Default")
      (node (ref "S11") (pin "2") (pinfunction "2_2") (pintype "passive"))
      (node (ref "S12") (pin "2") (pinfunction "2_2") (pintype "passive"))
      (node (ref "S13") (pin "2") (pinfunction "2_2") (pintype "passive"))
      (node (ref "S14") (pin "2") (pinfunction "2_2") (pintype "passive"))
      (node (ref "S15") (pin "2") (pinfunction "2_2") (pintype "passive"))
      (node (ref "S16") (pin "2") (pinfunction "2_2") (pintype "passive"))
      (node (ref "S17") (pin "2") (pinfunction "2_2") (pintype "passive"))
      (node (ref "S18") (pin "2") (pinfunction "2_2") (pintype "passive"))
      (node (ref "S19") (pin "2") (pinfunction "2_2") (pintype "passive"))
      (node (ref "S20") (pin "2") (pinfunction "2_2") (pintype "passive"))
    )
    (net (code "13") (name "/Row3") (class "Default")
      (node (ref "S21") (pin "2") (pinfunction "2_2") (pintype "passive"))
      (node (ref "S22") (pin "2") (pinfunction "2_2") (pintype "passive"))
      (node (ref "S23") (pin "2") (pinfunction "2_2") (pintype "passive"))
      (node (ref "S24") (pin "2") (pinfunction "2_2") (pintype "passive"))
      (node (ref "S25") (pin "2") (pinfunction "2_2") (pintype "passive"))
      (node (ref "S26") (pin "2") (pinfunction "2_2") (pintype "passive"))
      (node (ref "S27") (pin "2") (pinfunction "2_2") (pintype "passive"))
      (node (ref "S28") (pin "2") (pinfunction "2_2") (pintype "passive"))
      (node (ref "S29") (pin "2") (pinfunction "2_2") (pintype "passive"))
      (node (ref "S30") (pin "2") (pinfunction "2_2") (pintype "passive"))
    )
    (net (code "14") (name "/Row4") (class "Default")
      (node (ref "S31") (pin "2") (pinfunction "2_2") (pintype "passive"))
      (node (ref "S32") (pin "2") (pinfunction "2_2") (pintype "passive"))
      (node (ref "S33") (pin "2") (pinfunction "2_2") (pintype "passive"))
      (node (ref "S34") (pin "2") (pinfunction "2_2") (pintype "passive"))
      (node (ref "S35") (pin "2") (pinfunction "2_2") (pintype "passive"))
      (node (ref "S36") (pin "2") (pinfunction "2_2") (pintype "passive"))
      (node (ref "S37") (pin "2") (pinfunction "2_2") (pintype "passive"))
      (node (ref "S38") (pin "2") (pinfunction "2_2") (pintype "passive"))
      (node (ref "S39") (pin "2") (pinfunction "2_2") (pintype "passive"))
      (node (ref "S40") (pin "2") (pinfunction "2_2") (pintype "passive"))
    )
    (net (code "15") (name "/Row5") (class "Default")
      (node (ref "S41") (pin "2") (pinfunction "2_2") (pintype "passive"))
      (node (ref "S42") (pin "2") (pinfunction "2_2") (pintype "passive"))
      (node (ref "S43") (pin "2") (pinfunction "2_2") (pintype "passive"))
      (node (ref "S44") (pin "2") (pinfunction "2_2") (pintype "passive"))
      (node (ref "S45") (pin "2") (pinfunction "2_2") (pintype "passive"))
      (node (ref "S46") (pin "2") (pinfunction "2_2") (pintype "passive"))
      (node (ref "S47") (pin "2") (pinfunction "2_2") (pintype "passive"))
      (node (ref "S48") (pin "2") (pinfunction "2_2") (pintype "passive"))
      (node (ref "S49") (pin "2") (pinfunction "2_2") (pintype "passive"))
      (node (ref "S50") (pin "2") (pinfunction "2_2") (pintype "passive"))
    )
    (net (code "16") (name "/Row6") (class "Default")
      (node (ref "S51") (pin "2") (pinfunction "2_2") (pintype "passive"))
      (node (ref "S52") (pin "2") (pinfunction "2_2") (pintype "passive"))
      (node (ref "S53") (pin "2") (pinfunction "2_2") (pintype "passive"))
      (node (ref "S54") (pin "2") (pinfunction "2_2") (pintype "passive"))
      (node (ref "S55") (pin "2") (pinfunction "2_2") (pintype "passive"))
      (node (ref "S56") (pin "2") (pinfunction "2_2") (pintype "passive"))
      (node (ref "S57") (pin "2") (pinfunction "2_2") (pintype "passive"))
      (node (ref "S58") (pin "2") (pinfunction "2_2") (pintype "passive"))
      (node (ref "S59") (pin "2") (pinfunction "2_2") (pintype "passive"))
      (node (ref "S60") (pin "2") (pinfunction "2_2") (pintype "passive"))
    )
    (net (code "17") (name "/Row7") (class "Default")
      (node (ref "S61") (pin "2") (pinfunction "2_2") (pintype "passive"))
      (node (ref "S62") (pin "2") (pinfunction "2_2") (pintype "passive"))
      (node (ref "S63") (pin "2") (pinfunction "2_2") (pintype "passive"))
      (node (ref "S64") (pin "2") (pinfunction "2_2") (pintype "passive"))
      (node (ref "S65") (pin "2") (pinfunction "2_2") (pintype "passive"))
      (node (ref "S66") (pin "2") (pinfunction "2_2") (pintype "passive"))
      (node (ref "S67") (pin "2") (pinfunction "2_2") (pintype "passive"))
      (node (ref "S68") (pin "2") (pinfunction "2_2") (pintype "passive"))
      (node (ref "S69") (pin "2") (pinfunction "2_2") (pintype "passive"))
      (node (ref "S70") (pin "2") (pinfunction "2_2") (pintype "passive"))
    )
    (net (code "18") (name "/Row8") (class "Default")
      (node (ref "S71") (pin "2") (pinfunction "2_2") (pintype "passive"))
      (node (ref "S72") (pin "2") (pinfunction "2_2") (pintype "passive"))
      (node (ref "S73") (pin "2") (pinfunction "2_2") (pintype "passive"))
      (node (ref "S74") (pin "2") (pinfunction "2_2") (pintype "passive"))
      (node (ref "S75") (pin "2") (pinfunction "2_2") (pintype "passive"))
      (node (ref "S76") (pin "2") (pinfunction "2_2") (pintype "passive"))
      (node (ref "S77") (pin "2") (pinfunction "2_2") (pintype "passive"))
      (node (ref "S78") (pin "2") (pinfunction "2_2") (pintype "passive"))
      (node (ref "S79") (pin "2") (pinfunction "2_2") (pintype "passive"))
      (node (ref "S80") (pin "2") (pinfunction "2_2") (pintype "passive"))
    )
    (net (code "19") (name "/Row9") (class "Default")
      (node (ref "S81") (pin "2") (pinfunction "2_2") (pintype "passive"))
      (node (ref "S82") (pin "2") (pinfunction "2_2") (pintype "passive"))
      (node (ref "S83") (pin "2") (pinfunction "2_2") (pintype "passive"))
      (node (ref "S84") (pin "2") (pinfunction "2_2") (pintype "passive"))
      (node (ref "S85") (pin "2") (pinfunction "2_2") (pintype "passive"))
      (node (ref "S86") (pin "2") (pinfunction "2_2") (pintype "passive"))
      (node (ref "S87") (pin "2") (pinfunction "2_2") (pintype "passive"))
    )
    (net (code "20") (name "Net-(D1-K)") (class "Default")
      (node (ref "D1") (pin "2") (pinfunction "K_2") (pintype "passive"))
      (node (ref "S1") (pin "1") (pinfunction "1_1") (pintype "passive"))
    )
    (net (code "21") (name "Net-(D2-K)") (class "Default")
      (node (ref "D2") (pin "2") (pinfunction "K_2") (pintype "passive"))
      (node (ref "S2") (pin "1") (pinfunction "1_1") (pintype "passive"))
    )
    (net (code "22") (name "Net-(D3-K)") (class "Default")
      (node (ref "D3") (pin "2") (pinfunction "K_2") (pintype "passive"))
      (node (ref "S3") (pin "1") (pinfunction "1_1") (pintype "passive"))
    )
    (net (code "23") (name "Net-(D4-K)") (class "Default")
      (node (ref "D4") (pin "2") (pinfunction "K_2") (pintype "passive"))
      (node (ref "S4") (pin "1") (pinfunction "1_1") (pintype "passive"))
    )
    (net (code "24") (name "Net-(D5-K)") (class "Default")
      (node (ref "D5") (pin "2") (pinfunction "K_2") (pintype "passive"))
      (node (ref "S5") (pin "1") (pinfunction "1_1") (pintype "passive"))
    )
    (net (code "25") (name "Net-(D6-K)") (class "Default")
      (node (ref "D6") (pin "2") (pinfunction "K_2") (pintype "passive"))
      (node (ref "S6") (pin "1") (pinfunction "1_1") (pintype "passive"))
    )
    (net (code "26") (name "Net-(D7-K)") (class "Default")
      (node (ref "D7") (pin "2") (pinfunction "K_2") (pintype "passive"))
      (node (ref "S7") (pin "1") (pinfunction "1_1") (pintype "passive"))
    )
    (net (code "27") (name "Net-(D8-K)") (class "Default")
      (node (ref "D8") (pin "2") (pinfunction "K_2") (pintype "passive"))
      (node (ref "S8") (pin "1") (pinfunction "1_1") (pintype "passive"))
    )
    (net (code "28") (name "Net-(D9-K)") (class "Default")
      (node (ref "D9") (pin "2") (pinfunction "K_2") (pintype "passive"))
      (node (ref "S9") (pin "1") (pinfunction "1_1") (pintype "passive"))
    )
    (net (code "29") (name "Net-(D10-K)") (class "Default")
      (node (ref "D10") (pin "2") (pinfunction "K_2") (pintype "passive"))
      (node (ref "S10") (pin "1") (pinfunction "1_1") (pintype "passive"))
    )
    (net (code "30") (name "Net-(D11-K)") (class "Default")
      (node (ref "D11") (pin "2") (pinfunction "K_2") (pintype "passive"))
      (node (ref "S11") (pin "1") (pinfunction "1_1") (pintype "passive"))
    )
    (net (code "31") (name "Net-(D12-K)") (class "Default")
      (node (ref "D12") (pin "2") (pinfunction "K_2") (pintype "passive"))
      (node (ref "S12") (pin "1") (pinfunction "1_1") (pintype "passive"))
    )
    (net (code "32") (name "Net-(D13-K)") (class "Default")
      (node (ref "D13") (pin "2") (pinfunction "K_2") (pintype "passive"))
      (node (ref "S13") (pin "1") (pinfunction "1_1") (pintype "passive"))
    )
    (net (code "33") (name "Net-(D14-K)") (class "Default")
      (node (ref "D14") (pin "2") (pinfunction "K_2") (pintype "passive"))
      (node (ref "S14") (pin "1") (pinfunction "1_1") (pintype "passive"))
    )
    (net (code "34") (name "Net-(D15-K)") (class "Default")
      (node (ref "D15") (pin "2") (pinfunction "K_2") (pintype "passive"))
      (node (ref "S15") (pin "1") (pinfunction "1_1") (pintype "passive"))
    )
    (net (code "35") (name "Net-(D16-K)") (class "Default")
      (node (ref "D16") (pin "2") (pinfunction "K_2") (pintype "passive"))
      (node (ref "S16") (pin "1") (pinfunction "1_1") (pintype "passive"))
    )
    (net (code "36") (name "Net-(D17-K)") (class "Default")
      (node (ref "D17") (pin "2") (pinfunction "K_2") (pintype "passive"))
      (node (ref "S17") (pin "1") (pinfunction "1_1") (pintype "passive"))
    )
    (net (code "37") (name "Net-(D18-K)") (class "Default")
      (node (ref "D18") (pin "2") (pinfunction "K_2") (pintype "passive"))
      (node (ref "S18") (pin "1") (pinfunction "1_1") (pintype "passive"))
    )
    (net (code "38") (name "Net-(D19-K)") (class "Default")
      (node (ref "D19") (pin "2") (pinfunction "K_2") (pintype "passive"))
      (node (ref "S19") (pin "1") (pinfunction "1_1") (pintype "passive"))
    )
    (net (code "39") (name "Net-(D20-K)") (class "Default")
      (node (ref "D20") (pin "2") (pinfunction "K_2") (pintype "passive"))
      (node (ref "S20") (pin "1") (pinfunction "1_1") (pintype "passive"))
    )
    (net (code "40") (name "Net-(D21-K)") (class "Default")
      (node (ref "D21") (pin "2") (pinfunction "K_2") (pintype "passive"))
      (node (ref "S21") (pin "1") (pinfunction "1_1") (pintype "passive"))
    )
    (net (code "41") (name "Net-(D22-K)") (class "Default")
      (node (ref "D22") (pin "2") (pinfunction "K_2") (pintype "passive"))
      (node (ref "S22") (pin "1") (pinfunction "1_1") (pintype "passive"))
    )
    (net (code "42") (name "Net-(D23-K)") (class "Default")
      (node (ref "D23") (pin "2") (pinfunction "K_2") (pintype "passive"))
      (node (ref "S23") (pin "1") (pinfunction "1_1") (pintype "passive"))
    )
    (net (code "43") (name "Net-(D24-K)") (class "Default")
      (node (ref "D24") (pin "2") (pinfunction "K_2") (pintype "passive"))
      (node (ref "S24") (pin "1") (pinfunction "1_1") (pintype "passive"))
    )
    (net (code "44") (name "Net-(D25-K)") (class "Default")
      (node (ref "D25") (pin "2") (pinfunction "K_2") (pintype "passive"))
      (node (ref "S25") (pin "1") (pinfunction "1_1") (pintype "passive"))
    )
    (net (code "45") (name "Net-(D26-K)") (class "Default")
      (node (ref "D26") (pin "2") (pinfunction "K_2") (pintype "passive"))
      (node (ref "S26") (pin "1") (pinfunction "1_1") (pintype "passive"))
    )
    (net (code "46") (name "Net-(D27-K)") (class "Default")
      (node (ref "D27") (pin "2") (pinfunction "K_2") (pintype "passive"))
      (node (ref "S27") (pin "1") (pinfunction "1_1") (pintype "passive"))
    )
    (net (code "47") (name "Net-(D28-K)") (class "Default")
      (node (ref "D28") (pin "2") (pinfunction "K_2") (pintype "passive"))
      (node (ref "S28") (pin "1") (pinfunction "1_1") (pintype "passive"))
    )
    (net (code "48") (name "Net-(D29-K)") (class "Default")
      (node (ref "D29") (pin "2") (pinfunction "K_2") (pintype "passive"))
      (node (ref "S29") (pin "1") (pinfunction "1_1") (pintype "passive"))
    )
    (net (code "49") (name "Net-(D30-K)") (class "Default")
      (node (ref "D30") (pin "2") (pinfunction "K_2") (pintype "passive"))
      (node (ref "S30") (pin "1") (pinfunction "1_1") (pintype "passive"))
    )
    (net (code "50") (name "Net-(D31-K)") (class "Default")
      (node (ref "D31") (pin "2") (pinfunction "K_2") (pintype "passive"))
      (node (ref "S31") (pin "1") (pinfunction "1_1") (pintype "passive"))
    )
    (net (code "51") (name "Net-(D32-K)") (class "Default")
      (node (ref "D32") (pin "2") (pinfunction "K_2") (pintype "passive"))
      (node (ref "S32") (pin "1") (pinfunction "1_1") (pintype "passive"))
    )
    (net (code "52") (name "Net-(D33-K)") (class "Default")
      (node (ref "D33") (pin "2") (pinfunction "K_2") (pintype "passive"))
      (node (ref "S33") (pin "1") (pinfunction "1_1") (pintype "passive"))
    )
    (net (code "53") (name "Net-(D34-K)") (class "Default")
      (node (ref "D34") (pin "2") (pinfunction "K_2") (pintype "passive"))
      (node (ref "S34") (pin "1") (pinfunction "1_1") (pintype "passive"))
    )
    (net (code "54") (name "Net-(D35-K)") (class "Default")
      (node (ref "D35") (pin "2") (pinfunction "K_2") (pintype "passive"))
      (node (ref "S35") (pin "1") (pinfunction "1_1") (pintype "passive"))
    )
    (net (code "55") (name "Net-(D36-K)") (class "Default")
      (node (ref "D36") (pin "2") (pinfunction "K_2") (pintype "passive"))
      (node (ref "S36") (pin "1") (pinfunction "1_1") (pintype "passive"))
    )
    (net (code "56") (name "Net-(D37-K)") (class "Default")
      (node (ref "D37") (pin "2") (pinfunction "K_2") (pintype "passive"))
      (node (ref "S37") (pin "1") (pinfunction "1_1") (pintype "passive"))
    )
    (net (code "57") (name "Net-(D38-K)") (class "Default")
      (node (ref "D38") (pin "2") (pinfunction "K_2") (pintype "passive"))
      (node (ref "S38") (pin "1") (pinfunction "1_1") (pintype "passive"))
    )
    (net (code "58") (name "Net-(D39-K)") (class "Default")
      (node (ref "D39") (pin "2") (pinfunction "K_2") (pintype "passive"))
      (node (ref "S39") (pin "1") (pinfunction "1_1") (pintype "passive"))
    )
    (net (code "59") (name "Net-(D40-K)") (class "Default")
      (node (ref "D40") (pin "2") (pinfunction "K_2") (pintype "passive"))
      (node (ref "S40") (pin "1") (pinfunction "1_1") (pintype "passive"))
    )
    (net (code "60") (name "Net-(D41-K)") (class "Default")
      (node (ref "D41") (pin "2") (pinfunction "K_2") (pintype "passive"))
      (node (ref "S41") (pin "1") (pinfunction "1_1") (pintype "passive"))
    )
    (net (code "61") (name "Net-(D42-K)") (class "Default")
      (node (ref "D42") (pin "2") (pinfunction "K_2") (pintype "passive"))
      (node (ref "S42") (pin "1") (pinfunction "1_1") (pintype "passive"))
    )
    (net (code "62") (name "Net-(D43-K)") (class "Default")
      (node (ref "D43") (pin "2") (pinfunction "K_2") (pintype "passive"))
      (node (ref "S43") (pin "1") (pinfunction "1_1") (pintype "passive"))
    )
    (net (code "63") (name "Net-(D44-K)") (class "Default")
      (node (ref "D44") (pin "2") (pinfunction "K_2") (pintype "passive"))
      (node (ref "S44") (pin "1") (pinfunction "1_1") (pintype "passive"))
    )
    (net (code "64") (name "Net-(D45-K)") (class "Default")
      (node (ref "D45") (pin "2") (pinfunction "K_2") (pintype "passive"))
      (node (ref "S45") (pin "1") (pinfunction "1_1") (pintype "passive"))
    )
    (net (code "65") (name "Net-(D46-K)") (class "Default")
      (node (ref "D46") (pin "2") (pinfunction "K_2") (pintype "passive"))
      (node (ref "S46") (pin "1") (pinfunction "1_1") (pintype "passive"))
    )
    (net (code "66") (name "Net-(D47-K)") (class "Default")
      (node (ref "D47") (pin "2") (pinfunction "K_2") (pintype "passive"))
      (node (ref "S47") (pin "1") (pinfunction "1_1") (pintype "passive"))
    )
    (net (code "67") (name "Net-(D48-K)") (class "Default")
      (node (ref "D48") (pin "2") (pinfunction "K_2") (pintype "passive"))
      (node (ref "S48") (pin "1") (pinfunction "1_1") (pintype "passive"))
    )
    (net (code "68") (name "Net-(D49-K)") (class "Default")
      (node (ref "D49") (pin "2") (pinfunction "K_2") (pintype "passive"))
      (node (ref "S49") (pin "1") (pinfunction "1_1") (pintype "passive"))
    )
    (net (code "69") (name "Net-(D50-K)") (class "Default")
      (node (ref "D50") (pin "2") (pinfunction "K_2") (pintype "passive"))
      (node (ref "S50") (pin "1") (pinfunction "1_1") (pintype "passive"))
    )
    (net (code "70") (name "Net-(D51-K)") (class "Default")
      (node (ref "D51") (pin "2") (pinfunction "K_2") (pintype "passive"))
      (node (ref "S51") (pin "1") (pinfunction "1_1") (pintype "passive"))
    )
    (net (code "71") (name "Net-(D52-K)") (class "Default")
      (node (ref "D52") (pin "2") (pinfunction "K_2") (pintype "passive"))
      (node (ref "S52") (pin "1") (pinfunction "1_1") (pintype "passive"))
    )
    (net (code "72") (name "Net-(D53-K)") (class "Default")
      (node (ref "D53") (pin "2") (pinfunction "K_2") (pintype "passive"))
      (node (ref "S53") (pin "1") (pinfunction "1_1") (pintype "passive"))
    )
    (net (code "73") (name "Net-(D54-K)") (class "Default")
      (node (ref "D54") (pin "2") (pinfunction "K_2") (pintype "passive"))
      (node (ref "S54") (pin "1") (pinfunction "1_1") (pintype "passive"))
    )
    (net (code "74") (name "Net-(D55-K)") (class "Default")
      (node (ref "D55") (pin "2") (pinfunction "K_2") (pintype "passive"))
      (node (ref "S55") (pin "1") (pinfunction "1_1") (pintype "passive"))
    )
    (net (code "75") (name "Net-(D56-K)") (class "Default")
      (node (ref "D56") (pin "2") (pinfunction "K_2") (pintype "passive"))
      (node (ref "S56") (pin "1") (pinfunction "1_1") (pintype "passive"))
    )
    (net (code "76") (name "Net-(D57-K)") (class "Default")
      (node (ref "D57") (pin "2") (pinfunction "K_2") (pintype "passive"))
      (node (ref "S57") (pin "1") (pinfunction "1_1") (pintype "passive"))
    )
    (net (code "77") (name "Net-(D58-K)") (class "Default")
      (node (ref "D58") (pin "2") (pinfunction "K_2") (pintype "passive"))
      (node (ref "S58") (pin "1") (pinfunction "1_1") (pintype "passive"))
    )
    (net (code "78") (name "Net-(D59-K)") (class "Default")
      (node (ref "D59") (pin "2") (pinfunction "K_2") (pintype "passive"))
      (node (ref "S59") (pin "1") (pinfunction "1_1") (pintype "passive"))
    )
    (net (code "79") (name "Net-(D60-K)") (class "Default")
      (node (ref "D60") (pin "2") (pinfunction "K_2") (pintype "passive"))
      (node (ref "S60") (pin "1") (pinfunction "1_1") (pintype "passive"))
    )
    (net (code "80") (name "Net-(D61-K)") (class "Default")
      (node (ref "D61") (pin "2") (pinfunction "K_2") (pintype "passive"))
      (node (ref "S61") (pin "1") (pinfunction "1_1") (pintype "passive"))
    )
    (net (code "81") (name "Net-(D62-K)") (class "Default")
      (node (ref "D62") (pin "2") (pinfunction "K_2") (pintype "passive"))
      (node (ref "S62") (pin "1") (pinfunction "1_1") (pintype "passive"))
    )
    (net (code "82") (name "Net-(D63-K)") (class "Default")
      (node (ref "D63") (pin "2") (pinfunction "K_2") (pintype "passive"))
      (node (ref "S63") (pin "1") (pinfunction "1_1") (pintype "passive"))
    )
    (net (code "83") (name "Net-(D64-K)") (class "Default")
      (node (ref "D64") (pin "2") (pinfunction "K_2") (pintype "passive"))
      (node (ref "S64") (pin "1") (pinfunction "1_1") (pintype "passive"))
    )
    (net (code "84") (name "Net-(D65-K)") (class "Default")
      (node (ref "D65") (pin "2") (pinfunction "K_2") (pintype "passive"))
      (node (ref "S65") (pin "1") (pinfunction "1_1") (pintype "passive"))
    )
    (net (code "85") (name "Net-(D66-K)") (class "Default")
      (node (ref "D66") (pin "2") (pinfunction "K_2") (pintype "passive"))
      (node (ref "S66") (pin "1") (pinfunction "1_1") (pintype "passive"))
    )
    (net (code "86") (name "Net-(D67-K)") (class "Default")
      (node (ref "D67") (pin "2") (pinfunction "K_2") (pintype "passive"))
      (node (ref "S67") (pin "1") (pinfunction "1_1") (pintype "passive"))
    )
    (net (code "87") (name "Net-(D68-K)") (class "Default")
      (node (ref "D68") (pin "2") (pinfunction "K_2") (pintype "passive"))
      (node (ref "S68") (pin "1") (pinfunction "1_1") (pintype "passive"))
    )
    (net (code "88") (name "Net-(D69-K)") (class "Default")
      (node (ref "D69") (pin "2") (pinfunction "K_2") (pintype "passive"))
      (node (ref "S69") (pin "1") (pinfunction "1_1") (pintype "passive"))
    )
    (net (code "89") (name "Net-(D70-K)") (class "Default")
      (node (ref "D70") (pin "2") (pinfunction "K_2") (pintype "passive"))
      (node (ref "S70") (pin "1") (pinfunction "1_1") (pintype "passive"))
    )
    (net (code "90") (name "Net-(D71-K)") (class "Default")
      (node (ref "D71") (pin "2") (pinfunction "K_2") (pintype "passive"))
      (node (ref "S71") (pin "1") (pinfunction "1_1") (pintype "passive"))
    )
    (net (code "91") (name "Net-(D72-K)") (class "Default")
      (node (ref "D72") (pin "2") (pinfunction "K_2") (pintype "passive"))
      (node (ref "S72") (pin "1") (pinfunction "1_1") (pintype "passive"))
    )
    (net (code "92") (name "Net-(D73-K)") (class "Default")
      (node (ref "D73") (pin "2") (pinfunction "K_2") (pintype "passive"))
      (node (ref "S73") (pin "1") (pinfunction "1_1") (pintype "passive"))
    )
    (net (code "93") (name "Net-(D74-K)") (class "Default")
      (node (ref "D74") (pin "2") (pinfunction "K_2") (pintype "passive"))
      (node (ref "S74") (pin "1") (pinfunction "1_1") (pintype "passive"))
    )
    (net (code "94") (name "Net-(D75-K)") (class "Default")
      (node (ref "D75") (pin "2") (pinfunction "K_2") (pintype "passive"))
      (node (ref "S75") (pin "1") (pinfunction "1_1") (pintype "passive"))
    )
    (net (code "95") (name "Net-(D76-K)") (class "Default")
      (node (ref "D76") (pin "2") (pinfunction "K_2") (pintype "passive"))
      (node (ref "S76") (pin "1") (pinfunction "1_1") (pintype "passive"))
    )
    (net (code "96") (name "Net-(D77-K)") (class "Default")
      (node (ref "D77") (pin "2") (pinfunction "K_2") (pintype "passive"))
      (node (ref "S77") (pin "1") (pinfunction "1_1") (pintype "passive"))
    )
    (net (code "97") (name "Net-(D78-K)") (class "Default")
      (node (ref "D78") (pin "2") (pinfunction "K_2") (pintype "passive"))
      (node (ref "S78") (pin "1") (pinfunction "1_1") (pintype "passive"))
    )
    (net (code "98") (name "Net-(D79-K)") (class "Default")
      (node (ref "D79") (pin "2") (pinfunction "K_2") (pintype "passive"))
      (node (ref "S79") (pin "1") (pinfunction "1_1") (pintype "passive"))
    )
    (net (code "99") (name "Net-(D80-K)") (class "Default")
      (node (ref "D80") (pin "2") (pinfunction "K_2") (pintype "passive"))
      (node (ref "S80") (pin "1") (pinfunction "1_1") (pintype "passive"))
    )
    (net (code "100") (name "Net-(D81-K)") (class "Default")
      (node (ref "D81") (pin "2") (pinfunction "K_2") (pintype "passive"))
      (node (ref "S81") (pin "1") (pinfunction "1_1") (pintype "passive"))
    )
    (net (code "101") (name "Net-(D82-K)") (class "Default")
      (node (ref "D82") (pin "2") (pinfunction "K_2") (pintype "passive"))
      (node (ref "S82") (pin "1") (pinfunction "1_1") (pintype "passive"))
    )
    (net (code "102") (name "Net-(D83-K)") (class "Default")
      (node (ref "D83") (pin "2") (pinfunction "K_2") (pintype "passive"))
      (node (ref "S83") (pin "1") (pinfunction "1_1") (pintype "passive"))
    )
    (net (code "103") (name "Net-(D84-K)") (class "Default")
      (node (ref "D84") (pin "2") (pinfunction "K_2") (pintype "passive"))
      (node (ref "S84") (pin "1") (pinfunction "1_1") (pintype "passive"))
    )
    (net (code "104") (name "Net-(D85-K)") (class "Default")
      (node (ref "D85") (pin "2") (pinfunction "K_2") (pintype "passive"))
      (node (ref "S85") (pin "1") (pinfunction "1_1") (pintype "passive"))
    )
    (net (code "105") (name "Net-(D86-K)") (class "Default")
      (node (ref "D86") (pin "2") (pinfunction "K_2") (pintype "passive"))
      (node (ref "S86") (pin "1") (pinfunction "1_1") (pintype "passive"))
    )
    (net (code "106") (name "Net-(D87-K)") (class "Default")
      (node (ref "D87") (pin "2") (pinfunction "K_2") (pintype "passive"))
      (node (ref "S87") (pin "1") (pinfunction "1_1") (pintype "passive"))
    )
  )
)
